# Connector.net
KiCad netlist of a schematic drawn in Altium Designer
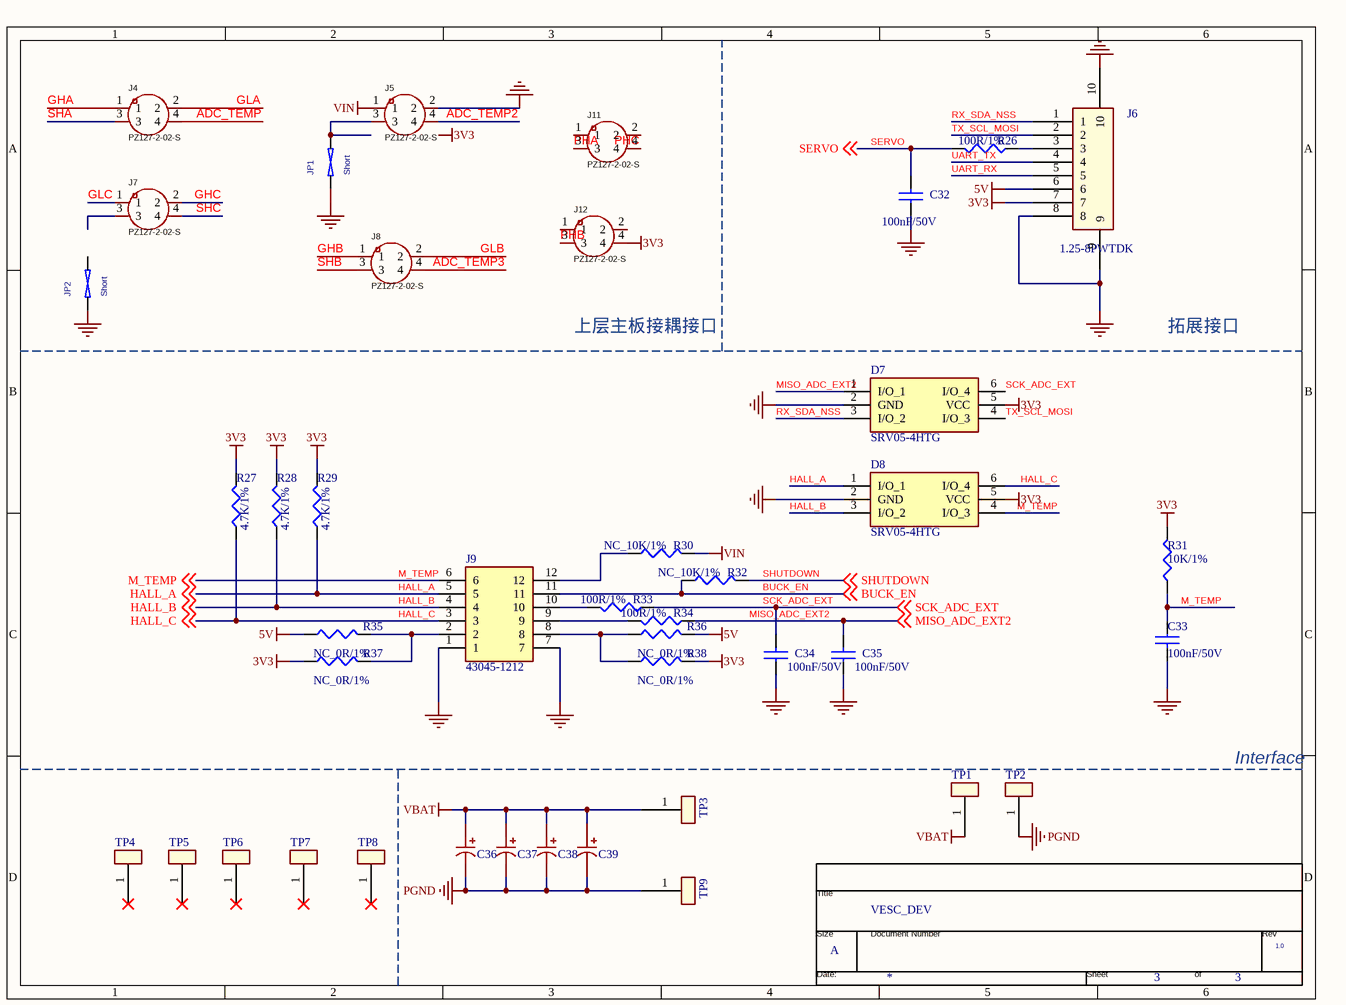
[diagram p0: Connector.SchDoc]

(export (version "E")
  (design (tool "Eeschema 10.0.6"))
  (components
    (comp (ref "C32") (value "100nF/50V") (footprint "C0402") (libsource (lib "*") (part "CAP NP")))
    (comp (ref "C33") (value "100nF/50V") (footprint "C0402") (libsource (lib "*") (part "CAP NP")))
    (comp (ref "C34") (value "100nF/50V") (footprint "C0402") (libsource (lib "*") (part "CAP NP")))
    (comp (ref "C35") (value "100nF/50V") (footprint "C0402") (libsource (lib "*") (part "CAP NP")))
    (comp (ref "C36")
      (value "680uF")
      (footprint "CAP-TH_BD10.0-P5.00-D0.6-FD")
      (description "容值:680uF;精度:±20%;额定电压:35V;纹波电流:-;等效串联电阻:-;")
      (fields (field (name "MANUFACTURER") "AISHI(艾华集团)") (field (name "MANUFACTURER PART") "ERS1VM681G16OT"))
      (libsource (lib "VESC_DEVICE_Library") (part "ERS1VM681G16OT"))
    )
    (comp (ref "C37")
      (value "680uF")
      (footprint "CAP-TH_BD10.0-P5.00-D0.6-FD")
      (description "容值:680uF;精度:±20%;额定电压:35V;纹波电流:-;等效串联电阻:-;")
      (fields (field (name "MANUFACTURER") "AISHI(艾华集团)") (field (name "MANUFACTURER PART") "ERS1VM681G16OT"))
      (libsource (lib "VESC_DEVICE_Library") (part "ERS1VM681G16OT"))
    )
    (comp (ref "C38")
      (value "680uF")
      (footprint "CAP-TH_BD10.0-P5.00-D0.6-FD")
      (description "容值:680uF;精度:±20%;额定电压:35V;纹波电流:-;等效串联电阻:-;")
      (fields (field (name "MANUFACTURER") "AISHI(艾华集团)") (field (name "MANUFACTURER PART") "ERS1VM681G16OT"))
      (libsource (lib "VESC_DEVICE_Library") (part "ERS1VM681G16OT"))
    )
    (comp (ref "C39")
      (value "680uF")
      (footprint "CAP-TH_BD10.0-P5.00-D0.6-FD")
      (description "容值:680uF;精度:±20%;额定电压:35V;纹波电流:-;等效串联电阻:-;")
      (fields (field (name "MANUFACTURER") "AISHI(艾华集团)") (field (name "MANUFACTURER PART") "ERS1VM681G16OT"))
      (libsource (lib "VESC_DEVICE_Library") (part "ERS1VM681G16OT"))
    )
    (comp (ref "D7")
      (value "SRV05-4HTG")
      (footprint "SamacSys:SOT95P280X145-6N")
      (description "TVS Diode (Uni-directional)")
      (fields (field (name "MOUSER PART NUMBER") "576-SRV05-4HTG"))
      (libsource (lib "VESC_DEVICE_Library") (part "SRV05-4HTG"))
    )
    (comp (ref "D8")
      (value "SRV05-4HTG")
      (footprint "SamacSys:SOT95P280X145-6N")
      (description "TVS Diode (Uni-directional)")
      (fields (field (name "MOUSER PART NUMBER") "576-SRV05-4HTG"))
      (libsource (lib "VESC_DEVICE_Library") (part "SRV05-4HTG"))
    )
    (comp (ref "J4")
      (value "PZ127-2-02-S")
      (footprint "HDR-SMD_4P-P1.27-V-M-R2-C2-LS5.3")
      (fields (field (name "MANUFACTURER") "HCTL(华灿天禄)"))
      (libsource (lib "VESC_DEVICE_Library") (part "PZ127-2-02-S"))
    )
    (comp (ref "J5")
      (value "PZ127-2-02-S")
      (footprint "HDR-SMD_4P-P1.27-V-M-R2-C2-LS5.3")
      (fields (field (name "MANUFACTURER") "HCTL(华灿天禄)"))
      (libsource (lib "VESC_DEVICE_Library") (part "PZ127-2-02-S"))
    )
    (comp (ref "J6")
      (value "1.25-8PWTDK")
      (footprint "SMD-8P-1_25")
      (libsource (lib "VESC_DEVICE_Library") (part "1.25-8PWTDK"))
    )
    (comp (ref "J7")
      (value "PZ127-2-02-S")
      (footprint "HDR-SMD_4P-P1.27-V-M-R2-C2-LS5.3")
      (fields (field (name "MANUFACTURER") "HCTL(华灿天禄)"))
      (libsource (lib "VESC_DEVICE_Library") (part "PZ127-2-02-S"))
    )
    (comp (ref "J8")
      (value "PZ127-2-02-S")
      (footprint "HDR-SMD_4P-P1.27-V-M-R2-C2-LS5.3")
      (fields (field (name "MANUFACTURER") "HCTL(华灿天禄)"))
      (libsource (lib "VESC_DEVICE_Library") (part "PZ127-2-02-S"))
    )
    (comp (ref "J9")
      (value "43045-1212")
      (footprint "SamacSys:43045-12YY_121314")
      (description "Connector")
      (fields (field (name "MOUSER PART NUMBER") "538-43045-1212"))
      (libsource (lib "VESC_DEVICE_Library") (part "43045-1212"))
    )
    (comp (ref "J11")
      (value "PZ127-2-02-S")
      (footprint "HDR-SMD_4P-P1.27-V-M-R2-C2-LS5.3")
      (fields (field (name "MANUFACTURER") "HCTL(华灿天禄)"))
      (libsource (lib "VESC_DEVICE_Library") (part "PZ127-2-02-S"))
    )
    (comp (ref "J12")
      (value "PZ127-2-02-S")
      (footprint "HDR-SMD_4P-P1.27-V-M-R2-C2-LS5.3")
      (fields (field (name "MANUFACTURER") "HCTL(华灿天禄)"))
      (libsource (lib "VESC_DEVICE_Library") (part "PZ127-2-02-S"))
    )
    (comp (ref "JP1")
      (value "Short")
      (footprint "SHORT")
      (description "2 PIN SHORTED TO CONNECT DIFFERENT NETS")
      (fields (field (name "PART_NUMBER") "TMP-442"))
      (libsource (lib "VESC_POWER_Library") (part "SHORT"))
    )
    (comp (ref "JP2")
      (value "Short")
      (footprint "SHORT")
      (description "2 PIN SHORTED TO CONNECT DIFFERENT NETS")
      (fields (field (name "PART_NUMBER") "TMP-442"))
      (libsource (lib "VESC_POWER_Library") (part "SHORT"))
    )
    (comp (ref "R26") (value "100R/1%") (footprint "R0402") (libsource (lib "*") (part "RESISTOR")))
    (comp (ref "R27") (value "4.7K/1%") (footprint "R0402") (libsource (lib "*") (part "RESISTOR")))
    (comp (ref "R28") (value "4.7K/1%") (footprint "R0402") (libsource (lib "*") (part "RESISTOR")))
    (comp (ref "R29") (value "4.7K/1%") (footprint "R0402") (libsource (lib "*") (part "RESISTOR")))
    (comp (ref "R30") (value "NC_10K/1%") (footprint "R0402") (libsource (lib "*") (part "RESISTOR")))
    (comp (ref "R31") (value "10K/1%") (footprint "R0402") (libsource (lib "*") (part "RESISTOR")))
    (comp (ref "R32") (value "NC_10K/1%") (footprint "R0402") (libsource (lib "*") (part "RESISTOR")))
    (comp (ref "R33") (value "100R/1%") (footprint "R0402") (libsource (lib "*") (part "RESISTOR")))
    (comp (ref "R34") (value "100R/1%") (footprint "R0402") (libsource (lib "*") (part "RESISTOR")))
    (comp (ref "R35") (value "NC_0R/1%") (footprint "R0402") (libsource (lib "*") (part "RESISTOR")))
    (comp (ref "R36") (value "NC_0R/1%") (footprint "R0402") (libsource (lib "*") (part "RESISTOR")))
    (comp (ref "R37") (value "NC_0R/1%") (footprint "R0402") (libsource (lib "*") (part "RESISTOR")))
    (comp (ref "R38") (value "NC_0R/1%") (footprint "R0402") (libsource (lib "*") (part "RESISTOR")))
    (comp (ref "TP1")
      (value "TEST POINT")
      (footprint "HOLE-4MM_M")
      (libsource (lib "VESC_DEVICE_Library") (part "TEST POINT"))
    )
    (comp (ref "TP2")
      (value "TEST POINT")
      (footprint "HOLE-4MM_M")
      (libsource (lib "VESC_DEVICE_Library") (part "TEST POINT"))
    )
    (comp (ref "TP3")
      (value "TEST POINT")
      (footprint "HOLE-8MM_M")
      (libsource (lib "") (part "TEST POINT_1"))
    )
    (comp (ref "TP4")
      (value "TEST POINT")
      (footprint "HOLE-4MM_M")
      (libsource (lib "VESC_DEVICE_Library") (part "TEST POINT"))
    )
    (comp (ref "TP5")
      (value "TEST POINT")
      (footprint "HOLE-4MM_M")
      (libsource (lib "VESC_DEVICE_Library") (part "TEST POINT"))
    )
    (comp (ref "TP6")
      (value "TEST POINT")
      (footprint "HOLE-8MM_M")
      (libsource (lib "VESC_DEVICE_Library") (part "TEST POINT"))
    )
    (comp (ref "TP7")
      (value "TEST POINT")
      (footprint "HOLE-8MM_M")
      (libsource (lib "VESC_DEVICE_Library") (part "TEST POINT"))
    )
    (comp (ref "TP8")
      (value "TEST POINT")
      (footprint "HOLE-8MM_M")
      (libsource (lib "VESC_DEVICE_Library") (part "TEST POINT"))
    )
    (comp (ref "TP9")
      (value "TEST POINT")
      (footprint "HOLE-8MM_M")
      (libsource (lib "") (part "TEST POINT_1"))
    )
  )
  (nets
    (net (code "1") (name "/ADC_TEMP") (class "Default")
      (node (ref "J4") (pin "4") (pinfunction "4_4") (pintype "passive"))
    )
    (net (code "2") (name "/ADC_TEMP2") (class "Default")
      (node (ref "J5") (pin "4") (pinfunction "4_4") (pintype "passive"))
    )
    (net (code "3") (name "/ADC_TEMP3") (class "Default")
      (node (ref "J8") (pin "4") (pinfunction "4_4") (pintype "passive"))
    )
    (net (code "4") (name "/GHA") (class "Default")
      (node (ref "J4") (pin "1") (pinfunction "1_1") (pintype "passive"))
    )
    (net (code "5") (name "/GHB") (class "Default")
      (node (ref "J8") (pin "1") (pinfunction "1_1") (pintype "passive"))
    )
    (net (code "6") (name "/GHC") (class "Default")
      (node (ref "J7") (pin "2") (pinfunction "2_2") (pintype "passive"))
    )
    (net (code "7") (name "/GLA") (class "Default")
      (node (ref "J4") (pin "2") (pinfunction "2_2") (pintype "passive"))
    )
    (net (code "8") (name "/GLB") (class "Default")
      (node (ref "J8") (pin "2") (pinfunction "2_2") (pintype "passive"))
    )
    (net (code "9") (name "/GLC") (class "Default")
      (node (ref "J7") (pin "1") (pinfunction "1_1") (pintype "passive"))
    )
    (net (code "10") (name "/PHA") (class "Default")
      (node (ref "J11") (pin "3") (pinfunction "3_3") (pintype "passive"))
    )
    (net (code "11") (name "/PHB") (class "Default")
      (node (ref "J12") (pin "3") (pinfunction "3_3") (pintype "passive"))
    )
    (net (code "12") (name "/PHC") (class "Default")
      (node (ref "J11") (pin "4") (pinfunction "4_4") (pintype "passive"))
    )
    (net (code "13") (name "/RX_SDA_NSS") (class "Default")
      (node (ref "D7") (pin "3") (pinfunction "I/O_2_3") (pintype "passive"))
      (node (ref "J6") (pin "1") (pinfunction "1_1") (pintype "passive"))
    )
    (net (code "14") (name "/SHA") (class "Default")
      (node (ref "J4") (pin "3") (pinfunction "3_3") (pintype "passive"))
    )
    (net (code "15") (name "/SHB") (class "Default")
      (node (ref "J8") (pin "3") (pinfunction "3_3") (pintype "passive"))
    )
    (net (code "16") (name "/SHC") (class "Default")
      (node (ref "J7") (pin "4") (pinfunction "4_4") (pintype "passive"))
    )
    (net (code "17") (name "/TX_SCL_MOSI") (class "Default")
      (node (ref "D7") (pin "4") (pinfunction "I/O_3_4") (pintype "passive"))
      (node (ref "J6") (pin "2") (pinfunction "2_2") (pintype "passive"))
    )
    (net (code "18") (name "/UART_RX") (class "Default")
      (node (ref "J6") (pin "5") (pinfunction "5_5") (pintype "passive"))
    )
    (net (code "19") (name "/UART_TX") (class "Default")
      (node (ref "J6") (pin "4") (pinfunction "4_4") (pintype "passive"))
    )
    (net (code "20") (name "3V3") (class "Default")
      (node (ref "D7") (pin "5") (pinfunction "VCC_5") (pintype "passive"))
      (node (ref "D8") (pin "5") (pinfunction "VCC_5") (pintype "passive"))
      (node (ref "J12") (pin "4") (pinfunction "4_4") (pintype "passive"))
      (node (ref "J6") (pin "7") (pinfunction "7_7") (pintype "passive"))
      (node (ref "R27") (pin "2") (pinfunction "2_2") (pintype "passive"))
      (node (ref "R28") (pin "2") (pinfunction "2_2") (pintype "passive"))
      (node (ref "R29") (pin "2") (pinfunction "2_2") (pintype "passive"))
      (node (ref "R31") (pin "2") (pinfunction "2_2") (pintype "passive"))
      (node (ref "R37") (pin "2") (pinfunction "2_2") (pintype "passive"))
      (node (ref "R38") (pin "1") (pinfunction "1_1") (pintype "passive"))
    )
    (net (code "21") (name "5V") (class "Default")
      (node (ref "J6") (pin "6") (pinfunction "6_6") (pintype "passive"))
      (node (ref "R35") (pin "2") (pinfunction "2_2") (pintype "passive"))
      (node (ref "R36") (pin "1") (pinfunction "1_1") (pintype "passive"))
    )
    (net (code "22") (name "BUCK_EN") (class "Default")
      (node (ref "J9") (pin "11") (pinfunction "11_11") (pintype "passive"))
      (node (ref "R32") (pin "2") (pinfunction "2_2") (pintype "passive"))
    )
    (net (code "23") (name "GND") (class "Default")
      (node (ref "C32") (pin "1") (pinfunction "1_1") (pintype "passive"))
      (node (ref "C33") (pin "2") (pinfunction "2_2") (pintype "passive"))
      (node (ref "C34") (pin "1") (pinfunction "1_1") (pintype "passive"))
      (node (ref "C35") (pin "1") (pinfunction "1_1") (pintype "passive"))
      (node (ref "D7") (pin "2") (pinfunction "GND_2") (pintype "passive"))
      (node (ref "D8") (pin "2") (pinfunction "GND_2") (pintype "passive"))
      (node (ref "J5") (pin "2") (pinfunction "2_2") (pintype "passive"))
      (node (ref "J6") (pin "10") (pinfunction "10_10") (pintype "passive"))
      (node (ref "J6") (pin "8") (pinfunction "8_8") (pintype "passive"))
      (node (ref "J6") (pin "9") (pinfunction "9_9") (pintype "passive"))
      (node (ref "J9") (pin "1") (pinfunction "1_1") (pintype "passive"))
      (node (ref "J9") (pin "7") (pinfunction "7_7") (pintype "passive"))
      (node (ref "JP1") (pin "1") (pinfunction "1_1") (pintype "passive"))
      (node (ref "JP2") (pin "1") (pinfunction "1_1") (pintype "passive"))
    )
    (net (code "24") (name "HALL_A") (class "Default")
      (node (ref "D8") (pin "1") (pinfunction "I/O_1_1") (pintype "passive"))
      (node (ref "J9") (pin "5") (pinfunction "5_5") (pintype "passive"))
      (node (ref "R29") (pin "1") (pinfunction "1_1") (pintype "passive"))
    )
    (net (code "25") (name "HALL_B") (class "Default")
      (node (ref "D8") (pin "3") (pinfunction "I/O_2_3") (pintype "passive"))
      (node (ref "J9") (pin "4") (pinfunction "4_4") (pintype "passive"))
      (node (ref "R28") (pin "1") (pinfunction "1_1") (pintype "passive"))
    )
    (net (code "26") (name "HALL_C") (class "Default")
      (node (ref "D8") (pin "6") (pinfunction "I/O_4_6") (pintype "passive"))
      (node (ref "J9") (pin "3") (pinfunction "3_3") (pintype "passive"))
      (node (ref "R27") (pin "1") (pinfunction "1_1") (pintype "passive"))
    )
    (net (code "27") (name "MISO_ADC_EXT2") (class "Default")
      (node (ref "C35") (pin "2") (pinfunction "2_2") (pintype "passive"))
      (node (ref "D7") (pin "1") (pinfunction "I/O_1_1") (pintype "passive"))
      (node (ref "R34") (pin "2") (pinfunction "2_2") (pintype "passive"))
    )
    (net (code "28") (name "M_TEMP") (class "Default")
      (node (ref "C33") (pin "1") (pinfunction "1_1") (pintype "passive"))
      (node (ref "D8") (pin "4") (pinfunction "I/O_3_4") (pintype "passive"))
      (node (ref "J9") (pin "6") (pinfunction "6_6") (pintype "passive"))
      (node (ref "R31") (pin "1") (pinfunction "1_1") (pintype "passive"))
    )
    (net (code "29") (name "Net-(J5-Pad3)") (class "Default")
      (node (ref "J5") (pin "3") (pinfunction "3_3") (pintype "passive"))
      (node (ref "JP1") (pin "2") (pinfunction "2_2") (pintype "passive"))
    )
    (net (code "30") (name "Net-(J6-Pad3)") (class "Default")
      (node (ref "J6") (pin "3") (pinfunction "3_3") (pintype "passive"))
      (node (ref "R26") (pin "2") (pinfunction "2_2") (pintype "passive"))
    )
    (net (code "31") (name "Net-(J9-Pad2)") (class "Default")
      (node (ref "J9") (pin "2") (pinfunction "2_2") (pintype "passive"))
      (node (ref "R35") (pin "1") (pinfunction "1_1") (pintype "passive"))
      (node (ref "R37") (pin "1") (pinfunction "1_1") (pintype "passive"))
    )
    (net (code "32") (name "Net-(J9-Pad8)") (class "Default")
      (node (ref "J9") (pin "8") (pinfunction "8_8") (pintype "passive"))
      (node (ref "R36") (pin "2") (pinfunction "2_2") (pintype "passive"))
      (node (ref "R38") (pin "2") (pinfunction "2_2") (pintype "passive"))
    )
    (net (code "33") (name "Net-(J9-Pad9)") (class "Default")
      (node (ref "J9") (pin "9") (pinfunction "9_9") (pintype "passive"))
      (node (ref "R34") (pin "1") (pinfunction "1_1") (pintype "passive"))
    )
    (net (code "34") (name "Net-(J9-Pad10)") (class "Default")
      (node (ref "J9") (pin "10") (pinfunction "10_10") (pintype "passive"))
      (node (ref "R33") (pin "1") (pinfunction "1_1") (pintype "passive"))
    )
    (net (code "35") (name "Net-(J9-Pad12)") (class "Default")
      (node (ref "J9") (pin "12") (pinfunction "12_12") (pintype "passive"))
      (node (ref "R30") (pin "2") (pinfunction "2_2") (pintype "passive"))
    )
    (net (code "36") (name "PGND") (class "Default")
      (node (ref "C36") (pin "2") (pinfunction "2_2") (pintype "passive"))
      (node (ref "C37") (pin "2") (pinfunction "2_2") (pintype "passive"))
      (node (ref "C38") (pin "2") (pinfunction "2_2") (pintype "passive"))
      (node (ref "C39") (pin "2") (pinfunction "2_2") (pintype "passive"))
      (node (ref "TP2") (pin "1") (pinfunction "1_1") (pintype "passive"))
      (node (ref "TP9") (pin "1") (pinfunction "1_1") (pintype "passive"))
    )
    (net (code "37") (name "SCK_ADC_EXT") (class "Default")
      (node (ref "C34") (pin "2") (pinfunction "2_2") (pintype "passive"))
      (node (ref "D7") (pin "6") (pinfunction "I/O_4_6") (pintype "passive"))
      (node (ref "R33") (pin "2") (pinfunction "2_2") (pintype "passive"))
    )
    (net (code "38") (name "SERVO") (class "Default")
      (node (ref "C32") (pin "2") (pinfunction "2_2") (pintype "passive"))
      (node (ref "R26") (pin "1") (pinfunction "1_1") (pintype "passive"))
    )
    (net (code "39") (name "SHUTDOWN") (class "Default")
      (node (ref "R32") (pin "1") (pinfunction "1_1") (pintype "passive"))
    )
    (net (code "40") (name "VBAT") (class "Default")
      (node (ref "C36") (pin "1") (pinfunction "1_1") (pintype "passive"))
      (node (ref "C37") (pin "1") (pinfunction "1_1") (pintype "passive"))
      (node (ref "C38") (pin "1") (pinfunction "1_1") (pintype "passive"))
      (node (ref "C39") (pin "1") (pinfunction "1_1") (pintype "passive"))
      (node (ref "TP1") (pin "1") (pinfunction "1_1") (pintype "passive"))
      (node (ref "TP3") (pin "1") (pinfunction "1_1") (pintype "passive"))
    )
    (net (code "41") (name "VIN") (class "Default")
      (node (ref "J5") (pin "1") (pinfunction "1_1") (pintype "passive"))
      (node (ref "R30") (pin "1") (pinfunction "1_1") (pintype "passive"))
    )
    (net (code "42") (name "unconnected-(J7-Pad3)") (class "Default")
      (node (ref "J7") (pin "3") (pinfunction "3_3") (pintype "passive"))
    )
    (net (code "43") (name "unconnected-(J11-Pad1)") (class "Default")
      (node (ref "J11") (pin "1") (pinfunction "1_1") (pintype "passive"))
    )
    (net (code "44") (name "unconnected-(J11-Pad2)") (class "Default")
      (node (ref "J11") (pin "2") (pinfunction "2_2") (pintype "passive"))
    )
    (net (code "45") (name "unconnected-(J12-Pad1)") (class "Default")
      (node (ref "J12") (pin "1") (pinfunction "1_1") (pintype "passive"))
    )
    (net (code "46") (name "unconnected-(J12-Pad2)") (class "Default")
      (node (ref "J12") (pin "2") (pinfunction "2_2") (pintype "passive"))
    )
    (net (code "47") (name "unconnected-(JP2-Pad2)") (class "Default")
      (node (ref "JP2") (pin "2") (pinfunction "2_2") (pintype "passive"))
    )
    (net (code "48") (name "unconnected-(TP4-Pad1)") (class "Default")
      (node (ref "TP4") (pin "1") (pinfunction "1_1") (pintype "passive+no_connect"))
    )
    (net (code "49") (name "unconnected-(TP5-Pad1)") (class "Default")
      (node (ref "TP5") (pin "1") (pinfunction "1_1") (pintype "passive+no_connect"))
    )
    (net (code "50") (name "unconnected-(TP6-Pad1)") (class "Default")
      (node (ref "TP6") (pin "1") (pinfunction "1_1") (pintype "passive+no_connect"))
    )
    (net (code "51") (name "unconnected-(TP7-Pad1)") (class "Default")
      (node (ref "TP7") (pin "1") (pinfunction "1_1") (pintype "passive+no_connect"))
    )
    (net (code "52") (name "unconnected-(TP8-Pad1)") (class "Default")
      (node (ref "TP8") (pin "1") (pinfunction "1_1") (pintype "passive+no_connect"))
    )
  )
)
